# Flash.net
KiCad netlist of a schematic drawn in Altium Designer
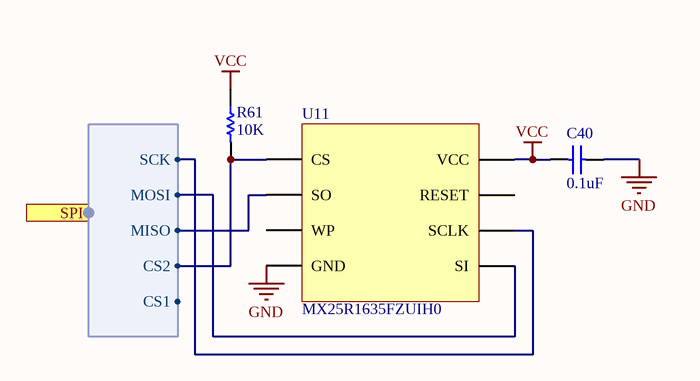
[diagram p0: Flash.SchDoc]

(export (version "E")
  (design (tool "Eeschema 10.0.6"))
  (components
    (comp (ref "C40")
      (value "0.1uF")
      (footprint "C0603[1608X92]")
      (description "0.1uF 6.3V 10% 0603 (1608 Metric)")
      (fields (field (name "PARTNUMBER") "GRM188R70J104KA01D") (field (name "MANUFACTURER") "Murata"))
      (libsource (lib "Capacitors") (part "CAP_0.1uF_6.3V_0603_10%"))
    )
    (comp (ref "R61")
      (value "10K")
      (footprint "R0603[1608]")
      (description "10K 0.25W 1% 0603 (1005 Metric)")
      (fields (field (name "MANUFACTURER") "Vishay") (field (name "PARTNUMBER") "RCS060310K0FKEA"))
      (libsource (lib "Resistors") (part "RES_10K_0603_1%"))
    )
    (comp (ref "U11")
      (value "MX25R1635FZUIH0")
      (footprint "USON-8")
      (fields (field (name "MANUFACTURER") "Macronix"))
      (libsource (lib "ICs") (part "MX25R1635FZUIH0"))
    )
  )
  (nets
    (net (code "2") (name "/CS2") (class "Default")
      (node (ref "R61") (pin "1") (pinfunction "1_1") (pintype "passive"))
      (node (ref "U11") (pin "1") (pinfunction "CS_1") (pintype "passive"))
    )
    (net (code "3") (name "/MISO") (class "Default")
      (node (ref "U11") (pin "2") (pinfunction "SO_2") (pintype "passive"))
    )
    (net (code "4") (name "/MOSI") (class "Default")
      (node (ref "U11") (pin "5") (pinfunction "SI_5") (pintype "power_in"))
    )
    (net (code "5") (name "/SCK") (class "Default")
      (node (ref "U11") (pin "6") (pinfunction "SCLK_6") (pintype "passive"))
    )
    (net (code "7") (name "GND") (class "Default")
      (node (ref "C40") (pin "2") (pinfunction "2_2") (pintype "passive"))
      (node (ref "U11") (pin "4") (pinfunction "GND_4") (pintype "passive"))
    )
    (net (code "8") (name "VCC") (class "Default")
      (node (ref "C40") (pin "1") (pinfunction "1_1") (pintype "passive"))
      (node (ref "R61") (pin "2") (pinfunction "2_2") (pintype "passive"))
      (node (ref "U11") (pin "8") (pinfunction "VCC_8") (pintype "passive"))
    )
    (net (code "9") (name "unconnected-(U11-RESET-Pad7)") (class "Default")
      (node (ref "U11") (pin "7") (pinfunction "RESET_7") (pintype "passive"))
    )
    (net (code "10") (name "unconnected-(U11-WP-Pad3)") (class "Default")
      (node (ref "U11") (pin "3") (pinfunction "WP_3") (pintype "passive"))
    )
  )
)
